# Vumetro-v2.net
KiCad netlist of a schematic drawn in EAGLE
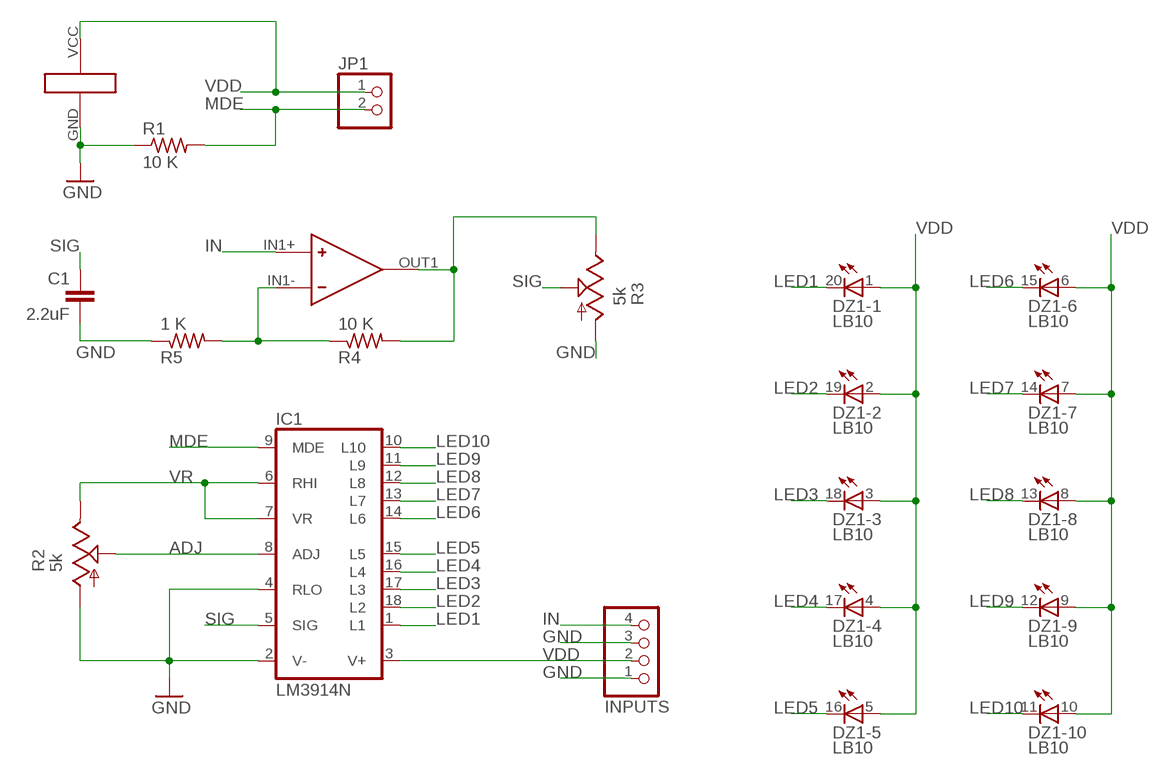
[diagram p0: schematic, sheet 1]

(export (version "E")
  (design (tool "Eeschema 10.0.6"))
  (components
    (comp (ref "C1")
      (value "2.2uF")
      (footprint "eagle-import:C2.5-6")
      (libsource (lib "eagle-import") (part "C2.5/6"))
    )
    (comp (ref "DZ1")
      (value "LB10")
      (footprint "eagle-import:LB10")
      (libsource (lib "eagle-import") (part "LB10"))
    )
    (comp (ref "IC1")
      (value "LM3914N")
      (footprint "eagle-import:DIL18")
      (libsource (lib "eagle-import") (part "LM3914N"))
    )
    (comp (ref "INPUTS")
      (value "PINHD-1X4")
      (footprint "eagle-import:1X04")
      (libsource (lib "eagle-import") (part "PINHD-1X4"))
    )
    (comp (ref "JP1")
      (value "PINHD-1X2")
      (footprint "eagle-import:1X02")
      (libsource (lib "eagle-import") (part "PINHD-1X2"))
    )
    (comp (ref "R1")
      (value "10 K")
      (footprint "eagle-import:0204_5")
      (libsource (lib "eagle-import") (part "R-US_0204/5"))
    )
    (comp (ref "R2")
      (value "5k")
      (footprint "eagle-import:PT-10")
      (libsource (lib "eagle-import") (part "TRIM_US-PT10"))
    )
    (comp (ref "R3")
      (value "5k")
      (footprint "eagle-import:PT-10")
      (libsource (lib "eagle-import") (part "TRIM_US-PT10"))
    )
    (comp (ref "R4")
      (value "10 K")
      (footprint "eagle-import:0204_5")
      (libsource (lib "eagle-import") (part "R-US_0204/5"))
    )
    (comp (ref "R5")
      (value "1 K")
      (footprint "eagle-import:0204_5")
      (libsource (lib "eagle-import") (part "R-US_0204/5"))
    )
    (comp (ref "U$1")
      (value "LM358")
      (footprint "eagle-import:LM358")
      (libsource (lib "eagle-import") (part "LM358"))
    )
  )
  (nets
    (net (code "1") (name "/ADJ") (class "Default")
      (node (ref "IC1") (pin "8") (pinfunction "ADJ_8") (pintype "input"))
      (node (ref "R2") (pin "S") (pinfunction "S_S") (pintype "passive"))
    )
    (net (code "2") (name "/IN") (class "Default")
      (node (ref "INPUTS") (pin "4") (pinfunction "4_4") (pintype "passive"))
      (node (ref "U$1") (pin "IN1+") (pinfunction "IN+_IN1+") (pintype "bidirectional"))
    )
    (net (code "3") (name "/LED1") (class "Default")
      (node (ref "DZ1") (pin "20") (pinfunction "C_20") (pintype "passive"))
      (node (ref "IC1") (pin "1") (pinfunction "L1_1") (pintype "output"))
    )
    (net (code "4") (name "/LED2") (class "Default")
      (node (ref "DZ1") (pin "19") (pinfunction "C_19") (pintype "passive"))
      (node (ref "IC1") (pin "18") (pinfunction "L2_18") (pintype "output"))
    )
    (net (code "5") (name "/LED3") (class "Default")
      (node (ref "DZ1") (pin "18") (pinfunction "C_18") (pintype "passive"))
      (node (ref "IC1") (pin "17") (pinfunction "L3_17") (pintype "output"))
    )
    (net (code "6") (name "/LED4") (class "Default")
      (node (ref "DZ1") (pin "17") (pinfunction "C_17") (pintype "passive"))
      (node (ref "IC1") (pin "16") (pinfunction "L4_16") (pintype "output"))
    )
    (net (code "7") (name "/LED5") (class "Default")
      (node (ref "DZ1") (pin "16") (pinfunction "C_16") (pintype "passive"))
      (node (ref "IC1") (pin "15") (pinfunction "L5_15") (pintype "output"))
    )
    (net (code "8") (name "/LED6") (class "Default")
      (node (ref "DZ1") (pin "15") (pinfunction "C_15") (pintype "passive"))
      (node (ref "IC1") (pin "14") (pinfunction "L6_14") (pintype "output"))
    )
    (net (code "9") (name "/LED7") (class "Default")
      (node (ref "DZ1") (pin "14") (pinfunction "C_14") (pintype "passive"))
      (node (ref "IC1") (pin "13") (pinfunction "L7_13") (pintype "output"))
    )
    (net (code "10") (name "/LED8") (class "Default")
      (node (ref "DZ1") (pin "13") (pinfunction "C_13") (pintype "passive"))
      (node (ref "IC1") (pin "12") (pinfunction "L8_12") (pintype "output"))
    )
    (net (code "11") (name "/LED9") (class "Default")
      (node (ref "DZ1") (pin "12") (pinfunction "C_12") (pintype "passive"))
      (node (ref "IC1") (pin "11") (pinfunction "L9_11") (pintype "output"))
    )
    (net (code "12") (name "/LED10") (class "Default")
      (node (ref "DZ1") (pin "11") (pinfunction "C_11") (pintype "passive"))
      (node (ref "IC1") (pin "10") (pinfunction "L10_10") (pintype "output"))
    )
    (net (code "13") (name "/MDE") (class "Default")
      (node (ref "IC1") (pin "9") (pinfunction "MDE_9") (pintype "input"))
      (node (ref "JP1") (pin "2") (pinfunction "2_2") (pintype "passive"))
      (node (ref "R1") (pin "2") (pinfunction "2_2") (pintype "passive"))
    )
    (net (code "14") (name "/SIG") (class "Default")
      (node (ref "C1") (pin "1") (pinfunction "1_1") (pintype "passive"))
      (node (ref "IC1") (pin "5") (pinfunction "SIG_5") (pintype "input"))
      (node (ref "R3") (pin "S") (pinfunction "S_S") (pintype "passive"))
    )
    (net (code "15") (name "/VDD") (class "Default")
      (node (ref "DZ1") (pin "1") (pinfunction "A_1") (pintype "passive"))
      (node (ref "DZ1") (pin "10") (pinfunction "A_10") (pintype "passive"))
      (node (ref "DZ1") (pin "2") (pinfunction "A_2") (pintype "passive"))
      (node (ref "DZ1") (pin "3") (pinfunction "A_3") (pintype "passive"))
      (node (ref "DZ1") (pin "4") (pinfunction "A_4") (pintype "passive"))
      (node (ref "DZ1") (pin "5") (pinfunction "A_5") (pintype "passive"))
      (node (ref "DZ1") (pin "6") (pinfunction "A_6") (pintype "passive"))
      (node (ref "DZ1") (pin "7") (pinfunction "A_7") (pintype "passive"))
      (node (ref "DZ1") (pin "8") (pinfunction "A_8") (pintype "passive"))
      (node (ref "DZ1") (pin "9") (pinfunction "A_9") (pintype "passive"))
      (node (ref "IC1") (pin "3") (pinfunction "V+_3") (pintype "power_in"))
      (node (ref "INPUTS") (pin "2") (pinfunction "2_2") (pintype "passive"))
      (node (ref "JP1") (pin "1") (pinfunction "1_1") (pintype "passive"))
      (node (ref "U$1") (pin "VCC") (pinfunction "VCC_VCC") (pintype "bidirectional"))
    )
    (net (code "16") (name "/VR") (class "Default")
      (node (ref "IC1") (pin "6") (pinfunction "RHI_6") (pintype "input"))
      (node (ref "IC1") (pin "7") (pinfunction "VR_7") (pintype "output"))
      (node (ref "R2") (pin "E") (pinfunction "E_E") (pintype "passive"))
    )
    (net (code "17") (name "GND") (class "Default")
      (node (ref "C1") (pin "2") (pinfunction "2_2") (pintype "passive"))
      (node (ref "IC1") (pin "2") (pinfunction "V-_2") (pintype "power_in"))
      (node (ref "IC1") (pin "4") (pinfunction "RLO_4") (pintype "input"))
      (node (ref "INPUTS") (pin "1") (pinfunction "1_1") (pintype "passive"))
      (node (ref "INPUTS") (pin "3") (pinfunction "3_3") (pintype "passive"))
      (node (ref "R1") (pin "1") (pinfunction "1_1") (pintype "passive"))
      (node (ref "R2") (pin "A") (pinfunction "A_A") (pintype "passive"))
      (node (ref "R3") (pin "A") (pinfunction "A_A") (pintype "passive"))
      (node (ref "R5") (pin "1") (pinfunction "1_1") (pintype "passive"))
      (node (ref "U$1") (pin "GND") (pinfunction "GND_GND") (pintype "bidirectional"))
    )
    (net (code "18") (name "Net-(U$1A-IN-)") (class "Default")
      (node (ref "R4") (pin "1") (pinfunction "1_1") (pintype "passive"))
      (node (ref "R5") (pin "2") (pinfunction "2_2") (pintype "passive"))
      (node (ref "U$1") (pin "IN1-") (pinfunction "IN-_IN1-") (pintype "bidirectional"))
    )
    (net (code "19") (name "Net-(U$1A-OUT)") (class "Default")
      (node (ref "R3") (pin "E") (pinfunction "E_E") (pintype "passive"))
      (node (ref "R4") (pin "2") (pinfunction "2_2") (pintype "passive"))
      (node (ref "U$1") (pin "OUT1") (pinfunction "OUT_OUT1") (pintype "bidirectional"))
    )
  )
)
